# Sheet1.net
KiCad netlist of a schematic drawn in Altium Designer
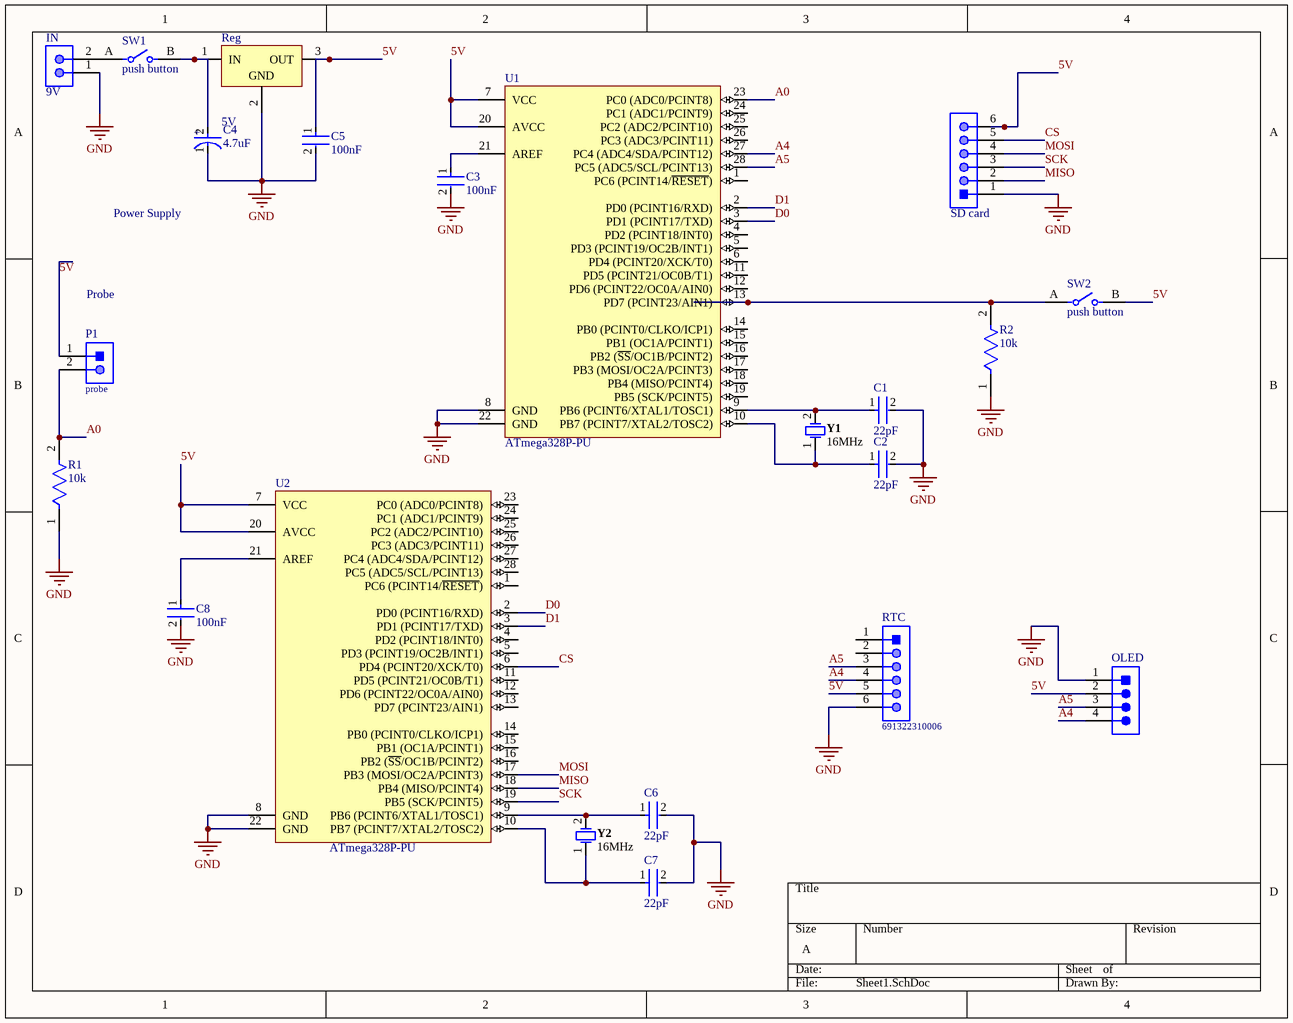
[diagram p0: Sheet1.SchDoc]

(export (version "E")
  (design (tool "Eeschema 10.0.6"))
  (components
    (comp (ref "C1")
      (value "22pF")
      (footprint "FP-RCE0DB-MFG")
      (description "Cap Ceramic 22pF 100V C0G ±5% Radial 2.5mm +125°C Ammo Pack")
      (fields (field (name "VOLTAGE") "100V") (field (name "TOLERANCE") "5%"))
      (libsource (lib "Altium Content Vault") (part "b4654b650e69147ec39a6b967a45e02"))
    )
    (comp (ref "C2")
      (value "22pF")
      (footprint "FP-RCE0DB-MFG")
      (description "Cap Ceramic 22pF 100V C0G ±5% Radial 2.5mm +125°C Ammo Pack")
      (fields (field (name "VOLTAGE") "100V") (field (name "TOLERANCE") "5%"))
      (libsource (lib "Altium Content Vault") (part "b4654b650e69147ec39a6b967a45e02"))
    )
    (comp (ref "C3")
      (value "100nF")
      (footprint "FP-RCE0DB-MFG")
      (description "Cap Ceramic 4.7nF 100V X7R ±10% Radial 2.5mm +125°C Ammo Pack")
      (fields (field (name "TOLERANCE") "10%"))
      (libsource (lib "Altium Content Vault") (part "b4654b650e69147ec39a6b967a45e02"))
    )
    (comp (ref "C4")
      (value "4.7uF")
      (footprint "FP-RAD-TH-D_6_3_0_5-L_11-MFG")
      (description "Aluminum Electrolytic Capacitors (Radial Lead Type) 4.7uF ±20% 160V")
      (fields (field (name "VOLTAGE") "160V") (field (name "TOLERANCE") "20%"))
      (libsource (lib "Altium Content Vault") (part "203bc49f2ac43e59fd269a8c329ed05"))
    )
    (comp (ref "C5")
      (value "100nF")
      (footprint "FP-C322C104K5R5TA-MFG")
      (description "CAP CER 0.1UF 50V X7R RADIAL")
      (fields (field (name "TOLERANCE") "10%") (field (name "VOLTAGE") "50V"))
      (libsource (lib "Altium Content Vault") (part "b4654b650e69147ec39a6b967a45e02"))
    )
    (comp (ref "C6")
      (value "22pF")
      (footprint "FP-RCE0DB-MFG")
      (description "Cap Ceramic 22pF 100V C0G ±5% Radial 2.5mm +125°C Ammo Pack")
      (fields (field (name "VOLTAGE") "100V") (field (name "TOLERANCE") "5%"))
      (libsource (lib "Altium Content Vault") (part "b4654b650e69147ec39a6b967a45e02"))
    )
    (comp (ref "C7")
      (value "22pF")
      (footprint "FP-RCE0DB-MFG")
      (description "Cap Ceramic 22pF 100V C0G ±5% Radial 2.5mm +125°C Ammo Pack")
      (fields (field (name "VOLTAGE") "100V") (field (name "TOLERANCE") "5%"))
      (libsource (lib "Altium Content Vault") (part "b4654b650e69147ec39a6b967a45e02"))
    )
    (comp (ref "C8")
      (value "100nF")
      (footprint "FP-RCE0DB-MFG")
      (description "Cap Ceramic 4.7nF 100V X7R ±10% Radial 2.5mm +125°C Ammo Pack")
      (fields (field (name "TOLERANCE") "10%"))
      (libsource (lib "Altium Content Vault") (part "b4654b650e69147ec39a6b967a45e02"))
    )
    (comp (ref "IN")
      (value "9V")
      (footprint "MOLX-22-27-2021_V")
      (fields (field (name "MANUFACTURER") "Molex") (field (name "PARTNUMBER") "0022272021"))
      (libsource (lib "Altium Content Vault") (part "CN-1P-M-R2"))
    )
    (comp (ref "OLED")
      (value "6")
      (footprint "TECO-640456-4")
      (description "Male Header, Pitch 2.54 mm, 1 x 4 Position, Height 10.03 mm, Tail Length 3.56 mm, RoHS, Bulk")
      (fields (field (name "MANUFACTURER") "TE Connectivity"))
      (libsource (lib "Altium Content Vault") (part "CN-1P-M-R4"))
    )
    (comp (ref "P1")
      (value "probe")
      (footprint "620302124022")
      (description "Male Shrouded Header WR-WTB, SMT, Vertical, pitch 2 mm, 1 x 2 position")
      (fields
        (field (name "MANUFACTURER") "Wurth Elektronik")
        (field (name "PART NUMBER") "620302124022")
        (field (name "PUBLISHER") "WurthElektronik")
      )
      (libsource (lib "Altium Content Vault") (part "WE-CN-1P-M-R2"))
    )
    (comp (ref "R1")
      (value "10k")
      (footprint "FP-CF18-MFG")
      (description "RES 10K OHM 1/8W 5% CF AXIAL")
      (fields
        (field (name "MANUFACTURER PART NUMBER") "CF18JT10K0")
        (field (name "MANUFACTURER") "Stackpole Electronics")
      )
      (libsource (lib "Altium Content Vault") (part "1029c3af85768c4190bb7ad29bc67b5"))
    )
    (comp (ref "R2")
      (value "10k")
      (footprint "FP-CF18-MFG")
      (description "RES 10K OHM 1/8W 5% CF AXIAL")
      (fields
        (field (name "MANUFACTURER PART NUMBER") "CF18JT10K0")
        (field (name "MANUFACTURER") "Stackpole Electronics")
      )
      (libsource (lib "Altium Content Vault") (part "1029c3af85768c4190bb7ad29bc67b5"))
    )
    (comp (ref "Reg")
      (value "5V")
      (footprint "TO220")
      (description "Positive Voltage Regulator, 6V, 3-Pin TO-220")
      (libsource (lib "Altium Content Vault") (part "PM-REG-L4940-SIL3"))
    )
    (comp (ref "RTC")
      (value "691322310006")
      (footprint "691322310006")
      (description "Serie 322 - 3.81mm Horizontal PCB Header WR-TBL, 6 pin")
      (fields (field (name "MANUFACTURER") "Wurth Elektronik") (field (name "PUBLISHER") "WurthElektronik"))
      (libsource (lib "Altium Content Vault") (part "WE-CN-1P-M-R6"))
    )
    (comp (ref "SD card")
      (value "66200611122")
      (footprint "66200611122")
      (description "THT Male Header WR-MPC3, Vertical, Single Row, pitch 3 mm, 6 pins")
      (fields (field (name "MANUFACTURER") "Wurth Elektronik") (field (name "PUBLISHER") "WurthElektronik"))
      (libsource (lib "") (part "WE-CN-1P-M-R6_1"))
    )
    (comp (ref "SW1")
      (value "push button")
      (footprint "FP-EVQ11Y04K-MFG")
      (description "SWITCH TACTILE SPST-NO 0.02A 15V")
      (libsource (lib "Altium Content Vault") (part "2b0b2b19372efd94fa7681498149756"))
    )
    (comp (ref "SW2")
      (value "push button")
      (footprint "FP-EVQ11Y04K-MFG")
      (description "SWITCH TACTILE SPST-NO 0.02A 15V")
      (libsource (lib "Altium Content Vault") (part "2b0b2b19372efd94fa7681498149756"))
    )
    (comp (ref "U1")
      (value "ATmega328P-PU")
      (footprint "28P3")
      (libsource (lib "Altium Content Vault") (part "MC-8B-ATM48-IL28"))
    )
    (comp (ref "U2")
      (value "ATmega328P-PU")
      (footprint "28P3")
      (libsource (lib "Altium Content Vault") (part "MC-8B-ATM48-IL28"))
    )
    (comp (ref "Y1")
      (value "16MHz")
      (footprint "FOX-FOXSLF160-20")
      (description "Resistance Weld Thru-Hole Crystal, 16 MHz, -20 to 70 degC, 2-Pin THD, RoHS, Bulk")
      (fields (field (name "TOLERANCE") "1%"))
      (libsource (lib "Altium Content Vault") (part "XTAL-1-2-2"))
    )
    (comp (ref "Y2")
      (value "16MHz")
      (footprint "FOX-FOXSLF160-20")
      (description "Resistance Weld Thru-Hole Crystal, 16 MHz, -20 to 70 degC, 2-Pin THD, RoHS, Bulk")
      (fields (field (name "TOLERANCE") "1%"))
      (libsource (lib "Altium Content Vault") (part "XTAL-1-2-2"))
    )
  )
  (nets
    (net (code "1") (name "/5V") (class "Default")
      (node (ref "C5") (pin "1") (pinfunction "1_1") (pintype "passive"))
      (node (ref "OLED") (pin "2") (pinfunction "2_2") (pintype "passive"))
      (node (ref "P1") (pin "1") (pinfunction "1_1") (pintype "passive"))
      (node (ref "RTC") (pin "5") (pinfunction "5_5") (pintype "passive"))
      (node (ref "Reg") (pin "3") (pinfunction "OUT_3") (pintype "power_in"))
      (node (ref "SD card") (pin "6") (pinfunction "6_6") (pintype "passive"))
      (node (ref "SW2") (pin "B") (pinfunction "B_B") (pintype "passive"))
      (node (ref "U1") (pin "20") (pinfunction "AVCC_20") (pintype "power_in"))
      (node (ref "U1") (pin "7") (pinfunction "VCC_7") (pintype "power_in"))
      (node (ref "U2") (pin "20") (pinfunction "AVCC_20") (pintype "power_in"))
      (node (ref "U2") (pin "7") (pinfunction "VCC_7") (pintype "power_in"))
    )
    (net (code "2") (name "/A0") (class "Default")
      (node (ref "P1") (pin "2") (pinfunction "2_2") (pintype "passive"))
      (node (ref "R1") (pin "2") (pinfunction "2_2") (pintype "passive"))
      (node (ref "U1") (pin "23") (pinfunction "PC0_(ADC0/PCINT8)_23") (pintype "bidirectional"))
    )
    (net (code "3") (name "/A4") (class "Default")
      (node (ref "OLED") (pin "4") (pinfunction "4_4") (pintype "passive"))
      (node (ref "RTC") (pin "4") (pinfunction "4_4") (pintype "passive"))
      (node (ref "U1") (pin "27") (pinfunction "PC4_(ADC4/SDA/PCINT12)_27") (pintype "bidirectional"))
    )
    (net (code "4") (name "/A5") (class "Default")
      (node (ref "OLED") (pin "3") (pinfunction "3_3") (pintype "passive"))
      (node (ref "RTC") (pin "3") (pinfunction "3_3") (pintype "passive"))
      (node (ref "U1") (pin "28") (pinfunction "PC5_(ADC5/SCL/PCINT13)_28") (pintype "bidirectional"))
    )
    (net (code "5") (name "/CS") (class "Default")
      (node (ref "SD card") (pin "5") (pinfunction "5_5") (pintype "passive"))
      (node (ref "U2") (pin "6") (pinfunction "PD4_(PCINT20/XCK/T0)_6") (pintype "bidirectional"))
    )
    (net (code "6") (name "/D0") (class "Default")
      (node (ref "U1") (pin "3") (pinfunction "PD1_(PCINT17/TXD)_3") (pintype "bidirectional"))
      (node (ref "U2") (pin "2") (pinfunction "PD0_(PCINT16/RXD)_2") (pintype "bidirectional"))
    )
    (net (code "7") (name "/D1") (class "Default")
      (node (ref "U1") (pin "2") (pinfunction "PD0_(PCINT16/RXD)_2") (pintype "bidirectional"))
      (node (ref "U2") (pin "3") (pinfunction "PD1_(PCINT17/TXD)_3") (pintype "bidirectional"))
    )
    (net (code "8") (name "/MISO") (class "Default")
      (node (ref "SD card") (pin "2") (pinfunction "2_2") (pintype "passive"))
      (node (ref "U2") (pin "18") (pinfunction "PB4_(MISO/PCINT4)_18") (pintype "bidirectional"))
    )
    (net (code "9") (name "/MOSI") (class "Default")
      (node (ref "SD card") (pin "4") (pinfunction "4_4") (pintype "passive"))
      (node (ref "U2") (pin "17") (pinfunction "PB3_(MOSI/OC2A/PCINT3)_17") (pintype "bidirectional"))
    )
    (net (code "10") (name "/SCK") (class "Default")
      (node (ref "SD card") (pin "3") (pinfunction "3_3") (pintype "passive"))
      (node (ref "U2") (pin "19") (pinfunction "PB5_(SCK/PCINT5)_19") (pintype "bidirectional"))
    )
    (net (code "11") (name "GND") (class "Default")
      (node (ref "C1") (pin "2") (pinfunction "2_2") (pintype "passive"))
      (node (ref "C2") (pin "2") (pinfunction "2_2") (pintype "passive"))
      (node (ref "C3") (pin "2") (pinfunction "2_2") (pintype "passive"))
      (node (ref "C4") (pin "1") (pinfunction "C_1") (pintype "passive"))
      (node (ref "C5") (pin "2") (pinfunction "2_2") (pintype "passive"))
      (node (ref "C6") (pin "2") (pinfunction "2_2") (pintype "passive"))
      (node (ref "C7") (pin "2") (pinfunction "2_2") (pintype "passive"))
      (node (ref "C8") (pin "2") (pinfunction "2_2") (pintype "passive"))
      (node (ref "IN") (pin "1") (pinfunction "1_1") (pintype "passive"))
      (node (ref "OLED") (pin "1") (pinfunction "1_1") (pintype "passive"))
      (node (ref "R1") (pin "1") (pinfunction "1_1") (pintype "passive"))
      (node (ref "R2") (pin "1") (pinfunction "1_1") (pintype "passive"))
      (node (ref "RTC") (pin "6") (pinfunction "6_6") (pintype "passive"))
      (node (ref "Reg") (pin "2") (pinfunction "GND_2") (pintype "power_in"))
      (node (ref "SD card") (pin "1") (pinfunction "1_1") (pintype "passive"))
      (node (ref "U1") (pin "22") (pinfunction "GND_22") (pintype "power_in"))
      (node (ref "U1") (pin "8") (pinfunction "GND_8") (pintype "power_in"))
      (node (ref "U2") (pin "22") (pinfunction "GND_22") (pintype "power_in"))
      (node (ref "U2") (pin "8") (pinfunction "GND_8") (pintype "power_in"))
    )
    (net (code "12") (name "Net-(C4-A)") (class "Default")
      (node (ref "C4") (pin "2") (pinfunction "A_2") (pintype "passive"))
      (node (ref "Reg") (pin "1") (pinfunction "IN_1") (pintype "power_in"))
      (node (ref "SW1") (pin "B") (pinfunction "B_B") (pintype "passive"))
    )
    (net (code "13") (name "Net-(IN-Pad2)") (class "Default")
      (node (ref "IN") (pin "2") (pinfunction "2_2") (pintype "passive"))
      (node (ref "SW1") (pin "A") (pinfunction "A_A") (pintype "passive"))
    )
    (net (code "14") (name "Net-(U1-AREF)") (class "Default")
      (node (ref "C3") (pin "1") (pinfunction "1_1") (pintype "passive"))
      (node (ref "U1") (pin "21") (pinfunction "AREF_21") (pintype "power_in"))
    )
    (net (code "15") (name "Net-(U1-PB6_(PCINT6{slash}XTAL1{slash}TOSC1))") (class "Default")
      (node (ref "C1") (pin "1") (pinfunction "1_1") (pintype "passive"))
      (node (ref "U1") (pin "9") (pinfunction "PB6_(PCINT6/XTAL1/TOSC1)_9") (pintype "bidirectional"))
      (node (ref "Y1") (pin "2") (pinfunction "2_2") (pintype "passive"))
    )
    (net (code "16") (name "Net-(U1-PB7_(PCINT7{slash}XTAL2{slash}TOSC2))") (class "Default")
      (node (ref "C2") (pin "1") (pinfunction "1_1") (pintype "passive"))
      (node (ref "U1") (pin "10") (pinfunction "PB7_(PCINT7/XTAL2/TOSC2)_10") (pintype "bidirectional"))
      (node (ref "Y1") (pin "1") (pinfunction "1_1") (pintype "passive"))
    )
    (net (code "17") (name "Net-(U1-PD7_(PCINT23{slash}AIN1))") (class "Default")
      (node (ref "R2") (pin "2") (pinfunction "2_2") (pintype "passive"))
      (node (ref "SW2") (pin "A") (pinfunction "A_A") (pintype "passive"))
      (node (ref "U1") (pin "13") (pinfunction "PD7_(PCINT23/AIN1)_13") (pintype "bidirectional"))
    )
    (net (code "18") (name "Net-(U2-AREF)") (class "Default")
      (node (ref "C8") (pin "1") (pinfunction "1_1") (pintype "passive"))
      (node (ref "U2") (pin "21") (pinfunction "AREF_21") (pintype "power_in"))
    )
    (net (code "19") (name "Net-(U2-PB6_(PCINT6{slash}XTAL1{slash}TOSC1))") (class "Default")
      (node (ref "C6") (pin "1") (pinfunction "1_1") (pintype "passive"))
      (node (ref "U2") (pin "9") (pinfunction "PB6_(PCINT6/XTAL1/TOSC1)_9") (pintype "bidirectional"))
      (node (ref "Y2") (pin "2") (pinfunction "2_2") (pintype "passive"))
    )
    (net (code "20") (name "Net-(U2-PB7_(PCINT7{slash}XTAL2{slash}TOSC2))") (class "Default")
      (node (ref "C7") (pin "1") (pinfunction "1_1") (pintype "passive"))
      (node (ref "U2") (pin "10") (pinfunction "PB7_(PCINT7/XTAL2/TOSC2)_10") (pintype "bidirectional"))
      (node (ref "Y2") (pin "1") (pinfunction "1_1") (pintype "passive"))
    )
    (net (code "21") (name "unconnected-(RTC-Pad1)") (class "Default")
      (node (ref "RTC") (pin "1") (pinfunction "1_1") (pintype "passive"))
    )
    (net (code "22") (name "unconnected-(RTC-Pad2)") (class "Default")
      (node (ref "RTC") (pin "2") (pinfunction "2_2") (pintype "passive"))
    )
    (net (code "23") (name "unconnected-(U1-PB0_(PCINT0{slash}CLKO{slash}ICP1)-Pad14)") (class "Default")
      (node (ref "U1") (pin "14") (pinfunction "PB0_(PCINT0/CLKO/ICP1)_14") (pintype "bidirectional"))
    )
    (net (code "24") (name "unconnected-(U1-PB1_(OC1A{slash}PCINT1)-Pad15)") (class "Default")
      (node (ref "U1") (pin "15") (pinfunction "PB1_(OC1A/PCINT1)_15") (pintype "bidirectional"))
    )
    (net (code "25") (name "unconnected-(U1-PB2_(~{SS}{slash}OC1B{slash}PCINT2)-Pad16)") (class "Default")
      (node (ref "U1") (pin "16") (pinfunction "PB2_(~{SS}/OC1B/PCINT2)_16") (pintype "bidirectional"))
    )
    (net (code "26") (name "unconnected-(U1-PB3_(MOSI{slash}OC2A{slash}PCINT3)-Pad17)") (class "Default")
      (node (ref "U1") (pin "17") (pinfunction "PB3_(MOSI/OC2A/PCINT3)_17") (pintype "bidirectional"))
    )
    (net (code "27") (name "unconnected-(U1-PB4_(MISO{slash}PCINT4)-Pad18)") (class "Default")
      (node (ref "U1") (pin "18") (pinfunction "PB4_(MISO/PCINT4)_18") (pintype "bidirectional"))
    )
    (net (code "28") (name "unconnected-(U1-PB5_(SCK{slash}PCINT5)-Pad19)") (class "Default")
      (node (ref "U1") (pin "19") (pinfunction "PB5_(SCK/PCINT5)_19") (pintype "bidirectional"))
    )
    (net (code "29") (name "unconnected-(U1-PC1_(ADC1{slash}PCINT9)-Pad24)") (class "Default")
      (node (ref "U1") (pin "24") (pinfunction "PC1_(ADC1/PCINT9)_24") (pintype "bidirectional"))
    )
    (net (code "30") (name "unconnected-(U1-PC2_(ADC2{slash}PCINT10)-Pad25)") (class "Default")
      (node (ref "U1") (pin "25") (pinfunction "PC2_(ADC2/PCINT10)_25") (pintype "bidirectional"))
    )
    (net (code "31") (name "unconnected-(U1-PC3_(ADC3{slash}PCINT11)-Pad26)") (class "Default")
      (node (ref "U1") (pin "26") (pinfunction "PC3_(ADC3/PCINT11)_26") (pintype "bidirectional"))
    )
    (net (code "32") (name "unconnected-(U1-PC6_(PCINT14{slash}~{RESET})-Pad1)") (class "Default")
      (node (ref "U1") (pin "1") (pinfunction "PC6_(PCINT14/~{RESET})_1") (pintype "bidirectional"))
    )
    (net (code "33") (name "unconnected-(U1-PD2_(PCINT18{slash}INT0)-Pad4)") (class "Default")
      (node (ref "U1") (pin "4") (pinfunction "PD2_(PCINT18/INT0)_4") (pintype "bidirectional"))
    )
    (net (code "34") (name "unconnected-(U1-PD3_(PCINT19{slash}OC2B{slash}INT1)-Pad5)") (class "Default")
      (node (ref "U1") (pin "5") (pinfunction "PD3_(PCINT19/OC2B/INT1)_5") (pintype "bidirectional"))
    )
    (net (code "35") (name "unconnected-(U1-PD4_(PCINT20{slash}XCK{slash}T0)-Pad6)") (class "Default")
      (node (ref "U1") (pin "6") (pinfunction "PD4_(PCINT20/XCK/T0)_6") (pintype "bidirectional"))
    )
    (net (code "36") (name "unconnected-(U1-PD5_(PCINT21{slash}OC0B{slash}T1)-Pad11)") (class "Default")
      (node (ref "U1") (pin "11") (pinfunction "PD5_(PCINT21/OC0B/T1)_11") (pintype "bidirectional"))
    )
    (net (code "37") (name "unconnected-(U1-PD6_(PCINT22{slash}OC0A{slash}AIN0)-Pad12)") (class "Default")
      (node (ref "U1") (pin "12") (pinfunction "PD6_(PCINT22/OC0A/AIN0)_12") (pintype "bidirectional"))
    )
    (net (code "38") (name "unconnected-(U2-PB0_(PCINT0{slash}CLKO{slash}ICP1)-Pad14)") (class "Default")
      (node (ref "U2") (pin "14") (pinfunction "PB0_(PCINT0/CLKO/ICP1)_14") (pintype "bidirectional"))
    )
    (net (code "39") (name "unconnected-(U2-PB1_(OC1A{slash}PCINT1)-Pad15)") (class "Default")
      (node (ref "U2") (pin "15") (pinfunction "PB1_(OC1A/PCINT1)_15") (pintype "bidirectional"))
    )
    (net (code "40") (name "unconnected-(U2-PB2_(~{SS}{slash}OC1B{slash}PCINT2)-Pad16)") (class "Default")
      (node (ref "U2") (pin "16") (pinfunction "PB2_(~{SS}/OC1B/PCINT2)_16") (pintype "bidirectional"))
    )
    (net (code "41") (name "unconnected-(U2-PC0_(ADC0{slash}PCINT8)-Pad23)") (class "Default")
      (node (ref "U2") (pin "23") (pinfunction "PC0_(ADC0/PCINT8)_23") (pintype "bidirectional"))
    )
    (net (code "42") (name "unconnected-(U2-PC1_(ADC1{slash}PCINT9)-Pad24)") (class "Default")
      (node (ref "U2") (pin "24") (pinfunction "PC1_(ADC1/PCINT9)_24") (pintype "bidirectional"))
    )
    (net (code "43") (name "unconnected-(U2-PC2_(ADC2{slash}PCINT10)-Pad25)") (class "Default")
      (node (ref "U2") (pin "25") (pinfunction "PC2_(ADC2/PCINT10)_25") (pintype "bidirectional"))
    )
    (net (code "44") (name "unconnected-(U2-PC3_(ADC3{slash}PCINT11)-Pad26)") (class "Default")
      (node (ref "U2") (pin "26") (pinfunction "PC3_(ADC3/PCINT11)_26") (pintype "bidirectional"))
    )
    (net (code "45") (name "unconnected-(U2-PC4_(ADC4{slash}SDA{slash}PCINT12)-Pad27)") (class "Default")
      (node (ref "U2") (pin "27") (pinfunction "PC4_(ADC4/SDA/PCINT12)_27") (pintype "bidirectional"))
    )
    (net (code "46") (name "unconnected-(U2-PC5_(ADC5{slash}SCL{slash}PCINT13)-Pad28)") (class "Default")
      (node (ref "U2") (pin "28") (pinfunction "PC5_(ADC5/SCL/PCINT13)_28") (pintype "bidirectional"))
    )
    (net (code "47") (name "unconnected-(U2-PC6_(PCINT14{slash}~{RESET})-Pad1)") (class "Default")
      (node (ref "U2") (pin "1") (pinfunction "PC6_(PCINT14/~{RESET})_1") (pintype "bidirectional"))
    )
    (net (code "48") (name "unconnected-(U2-PD2_(PCINT18{slash}INT0)-Pad4)") (class "Default")
      (node (ref "U2") (pin "4") (pinfunction "PD2_(PCINT18/INT0)_4") (pintype "bidirectional"))
    )
    (net (code "49") (name "unconnected-(U2-PD3_(PCINT19{slash}OC2B{slash}INT1)-Pad5)") (class "Default")
      (node (ref "U2") (pin "5") (pinfunction "PD3_(PCINT19/OC2B/INT1)_5") (pintype "bidirectional"))
    )
    (net (code "50") (name "unconnected-(U2-PD5_(PCINT21{slash}OC0B{slash}T1)-Pad11)") (class "Default")
      (node (ref "U2") (pin "11") (pinfunction "PD5_(PCINT21/OC0B/T1)_11") (pintype "bidirectional"))
    )
    (net (code "51") (name "unconnected-(U2-PD6_(PCINT22{slash}OC0A{slash}AIN0)-Pad12)") (class "Default")
      (node (ref "U2") (pin "12") (pinfunction "PD6_(PCINT22/OC0A/AIN0)_12") (pintype "bidirectional"))
    )
    (net (code "52") (name "unconnected-(U2-PD7_(PCINT23{slash}AIN1)-Pad13)") (class "Default")
      (node (ref "U2") (pin "13") (pinfunction "PD7_(PCINT23/AIN1)_13") (pintype "bidirectional"))
    )
  )
)
